# DRV8301.net
KiCad netlist of a schematic drawn in Altium Designer
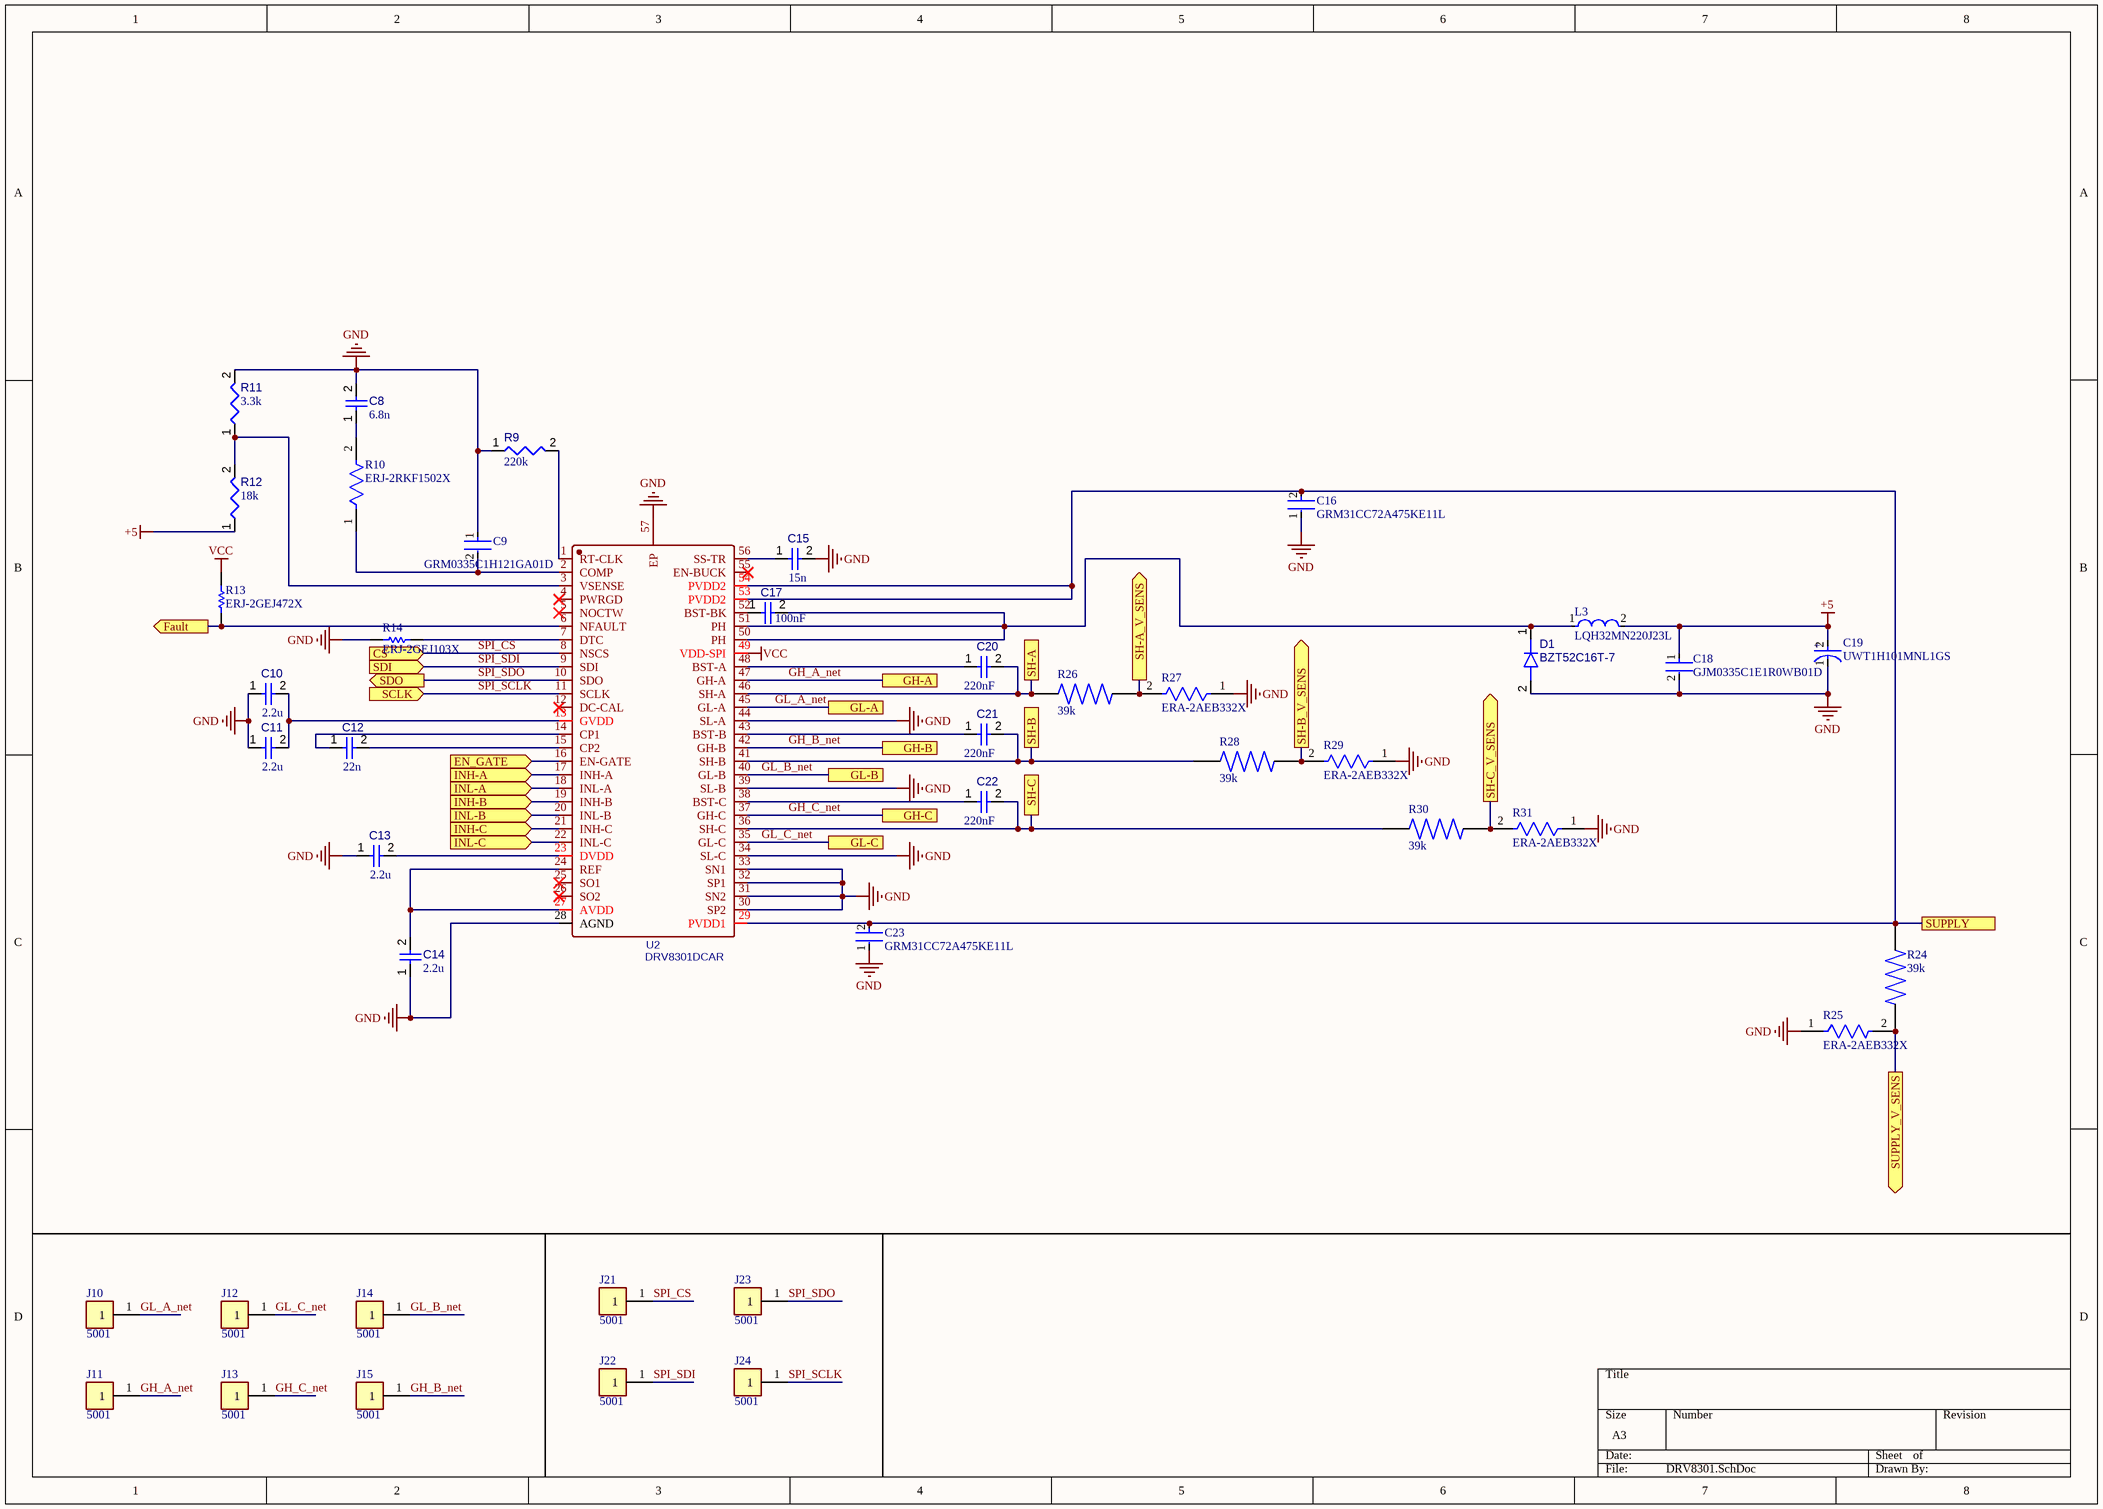
[diagram p0: DRV8301.SchDoc]

(export (version "E")
  (design (tool "Eeschema 10.0.6"))
  (components
    (comp (ref "C8")
      (value "6.8n")
      (footprint "CAP-0402")
      (fields (field (name "Comment") "C0402C682K5RECAUTO"))
      (libsource (lib "University of Michigan") (part "CAP-NP-2"))
    )
    (comp (ref "C9")
      (value "GRM0335C1H121GA01D")
      (footprint "FP-GRM033-0_03-IPC_A")
      (description "Chip Multilayer Ceramic Capacitors for General Purpose, 0201, 120pF, C0G, 30ppm/°C, 2%, 50V")
      (fields (field (name "TOLERANCE") "2%"))
      (libsource (lib "Altium Content Vault") (part "b4654b650e69147ec39a6b967a45e02"))
    )
    (comp (ref "C10")
      (value "2.2u")
      (footprint "CAP-0805")
      (description "ESD SMD Comm X7R 0805 (2012Metric) Ceramic Capacitor 0.079Lx0.049W 2.00mmx1.25mm X7R ±5% 2.2muF")
      (fields (field (name "Comment") "C0805C225J4REC7800"))
      (libsource (lib "University of Michigan") (part "CAP-NP-2"))
    )
    (comp (ref "C11")
      (value "2.2u")
      (footprint "CAP-0805")
      (description "ESD SMD Comm X7R 0805 (2012Metric) Ceramic Capacitor 0.079Lx0.049W 2.00mmx1.25mm X7R ±5% 2.2muF")
      (fields (field (name "Comment") "C0805C225J4REC7800"))
      (libsource (lib "University of Michigan") (part "CAP-NP-2"))
    )
    (comp (ref "C12")
      (value "22n")
      (footprint "CAP-0402")
      (fields (field (name "Comment") "C0402C223K5RECAUTO"))
      (libsource (lib "University of Michigan") (part "CAP-NP-2"))
    )
    (comp (ref "C13")
      (value "2.2u")
      (footprint "CAP-0805")
      (description "ESD SMD Comm X7R 0805 (2012Metric) Ceramic Capacitor 0.079Lx0.049W 2.00mmx1.25mm X7R ±5% 2.2muF")
      (fields (field (name "Comment") "C0805C225J4REC7800"))
      (libsource (lib "University of Michigan") (part "CAP-NP-2"))
    )
    (comp (ref "C14")
      (value "2.2u")
      (footprint "CAP-0805")
      (description "ESD SMD Comm X7R 0805 (2012Metric) Ceramic Capacitor 0.079Lx0.049W 2.00mmx1.25mm X7R ±5% 2.2muF")
      (fields (field (name "Comment") "C0805C225J4REC7800"))
      (libsource (lib "University of Michigan") (part "CAP-NP-2"))
    )
    (comp (ref "C15")
      (value "15n")
      (footprint "CAP-0402")
      (fields (field (name "Comment") "C0402C153J5REC7867"))
      (libsource (lib "University of Michigan") (part "CAP-NP-2"))
    )
    (comp (ref "C16")
      (value "GRM31CC72A475KE11L")
      (footprint "FP-GRM31C-0_3-e0_3_0_9-MFG")
      (description "Chip Multilayer Ceramic Capacitors for General Purpose, 1206, 4.7uF, X7S, 22%, 10%, 100V")
      (libsource (lib "Altium Content Vault") (part "f23184f103b6ebe33a8c269c53dcba6"))
    )
    (comp (ref "C17")
      (value "100nF")
      (footprint "CAP-0805")
      (description "Cap. SMD, 0805, X7R, 100nF, 20%, 50V,")
      (fields (field (name "Comment") "MT05B104M500BD"))
      (libsource (lib "University of Michigan") (part "CAP-NP-2"))
    )
    (comp (ref "C18")
      (value "GJM0335C1E1R0WB01D")
      (footprint "FP-GJM033-0_03-IPC_A")
      (description "Ceramic Capacitor 1pF ±0.05pF 25V C0G 0201 (0603 Metric)")
      (libsource (lib "Altium Content Vault") (part "b4654b650e69147ec39a6b967a45e02"))
    )
    (comp (ref "C19")
      (value "UWT1H101MNL1GS")
      (footprint "FP-UWT1H101MNL1GS-MFG")
      (description "CAP ALUM 100UF 20% 50V SMD")
      (fields (field (name "TOLERANCE") "20%") (field (name "VOLTAGE") "50V"))
      (libsource (lib "Altium Content Vault") (part "203bc49f2ac43e59fd269a8c329ed05"))
    )
    (comp (ref "C20")
      (value "220nF")
      (footprint "CAP-0805")
      (description "Cap Ceramic 0.22uF 100V X7R 5% SMD 0805 125°C T/R")
      (fields (field (name "Comment") "C0805C224J1REC7800"))
      (libsource (lib "University of Michigan") (part "CAP-NP-2"))
    )
    (comp (ref "C21")
      (value "220nF")
      (footprint "CAP-0805")
      (description "Cap Ceramic 0.22uF 100V X7R 5% SMD 0805 125°C T/R")
      (fields (field (name "Comment") "C0805C224J1REC7800"))
      (libsource (lib "University of Michigan") (part "CAP-NP-2"))
    )
    (comp (ref "C22")
      (value "220nF")
      (footprint "CAP-0805")
      (description "Cap Ceramic 0.22uF 100V X7R 5% SMD 0805 125°C T/R")
      (fields (field (name "Comment") "C0805C224J1REC7800"))
      (libsource (lib "University of Michigan") (part "CAP-NP-2"))
    )
    (comp (ref "C23")
      (value "GRM31CC72A475KE11L")
      (footprint "FP-GRM31C-0_3-e0_3_0_9-MFG")
      (description "Chip Multilayer Ceramic Capacitors for General Purpose, 1206, 4.7uF, X7S, 22%, 10%, 100V")
      (libsource (lib "Altium Content Vault") (part "f23184f103b6ebe33a8c269c53dcba6"))
    )
    (comp (ref "D1")
      (value "BZT52C16T-7")
      (footprint "SODFL160X65-2N")
      (description "Zener Diode, 16V V(Z), 5.56%, 0.3W, Silicon, Unidirectional")
      (libsource (lib "University of Michigan") (part "DIODE-2"))
    )
    (comp (ref "J10")
      (value "5001")
      (footprint "FP-5001-MFG")
      (description "PC TEST POINT MINIATURE BLACK")
      (libsource (lib "Altium Content Vault") (part "1e4615820a309e3ce90f9e6d957b7fa"))
    )
    (comp (ref "J11")
      (value "5001")
      (footprint "FP-5001-MFG")
      (description "PC TEST POINT MINIATURE BLACK")
      (libsource (lib "Altium Content Vault") (part "1e4615820a309e3ce90f9e6d957b7fa"))
    )
    (comp (ref "J12")
      (value "5001")
      (footprint "FP-5001-MFG")
      (description "PC TEST POINT MINIATURE BLACK")
      (libsource (lib "Altium Content Vault") (part "1e4615820a309e3ce90f9e6d957b7fa"))
    )
    (comp (ref "J13")
      (value "5001")
      (footprint "FP-5001-MFG")
      (description "PC TEST POINT MINIATURE BLACK")
      (libsource (lib "Altium Content Vault") (part "1e4615820a309e3ce90f9e6d957b7fa"))
    )
    (comp (ref "J14")
      (value "5001")
      (footprint "FP-5001-MFG")
      (description "PC TEST POINT MINIATURE BLACK")
      (libsource (lib "Altium Content Vault") (part "1e4615820a309e3ce90f9e6d957b7fa"))
    )
    (comp (ref "J15")
      (value "5001")
      (footprint "FP-5001-MFG")
      (description "PC TEST POINT MINIATURE BLACK")
      (libsource (lib "Altium Content Vault") (part "1e4615820a309e3ce90f9e6d957b7fa"))
    )
    (comp (ref "J21")
      (value "5001")
      (footprint "FP-5001-MFG")
      (description "PC TEST POINT MINIATURE BLACK")
      (libsource (lib "Altium Content Vault") (part "1e4615820a309e3ce90f9e6d957b7fa"))
    )
    (comp (ref "J22")
      (value "5001")
      (footprint "FP-5001-MFG")
      (description "PC TEST POINT MINIATURE BLACK")
      (libsource (lib "Altium Content Vault") (part "1e4615820a309e3ce90f9e6d957b7fa"))
    )
    (comp (ref "J23")
      (value "5001")
      (footprint "FP-5001-MFG")
      (description "PC TEST POINT MINIATURE BLACK")
      (libsource (lib "Altium Content Vault") (part "1e4615820a309e3ce90f9e6d957b7fa"))
    )
    (comp (ref "J24")
      (value "5001")
      (footprint "FP-5001-MFG")
      (description "PC TEST POINT MINIATURE BLACK")
      (libsource (lib "Altium Content Vault") (part "1e4615820a309e3ce90f9e6d957b7fa"))
    )
    (comp (ref "L3")
      (value "LQH32MN220J23L")
      (footprint "FP-LQH32CH_23-MFG")
      (description "Wire Wound Ferrite Inductor for General Circuits 22μH ±5% 2.8Ω 150mA 1210")
      (fields (field (name "TOLERANCE") "5%"))
      (libsource (lib "Altium Content Vault") (part "725321dda6339637d4d059423bc1c3c"))
    )
    (comp (ref "R9")
      (value "220k")
      (footprint "CAP-0603")
      (fields
        (field (name "POWER") "100mW")
        (field (name "TOLERANCE") "1%")
        (field (name "Comment") "WR06X2203FTL")
      )
      (libsource (lib "University of Michigan") (part "RES-2"))
    )
    (comp (ref "R10")
      (value "ERJ-2RKF1502X")
      (footprint "FP-ERJ2R-MFG")
      (description "RES SMD 15K OHM 1% 1/10W 0402")
      (fields
        (field (name "TOLERANCE") "1%")
        (field (name "OCTOPART") "https://octopart.com/erj-2rkf1502x-panasonic-55404985")
      )
      (libsource (lib "Altium Content Vault") (part "1029c3af85768c4190bb7ad29bc67b5"))
    )
    (comp (ref "R11")
      (value "3.3k")
      (footprint "CAP-0603")
      (fields
        (field (name "TOLERANCE") "1%")
        (field (name "POWER") "100mW")
        (field (name "Comment") "RMCF0603FT3K30")
      )
      (libsource (lib "University of Michigan") (part "RES-2"))
    )
    (comp (ref "R12")
      (value "18k")
      (footprint "CAP-0603")
      (fields
        (field (name "POWER") "100mW")
        (field (name "TOLERANCE") "1%")
        (field (name "Comment") "RMCF0603FT18K0")
      )
      (libsource (lib "University of Michigan") (part "RES-2"))
    )
    (comp (ref "R13")
      (value "ERJ-2GEJ472X")
      (footprint "RESC1005X40X25LL05T05")
      (fields (field (name "MANUFACTURER") "Panasonic"))
      (libsource (lib "Altium Content Vault") (part "RES"))
    )
    (comp (ref "R14")
      (value "ERJ-2GEJ103X")
      (footprint "RESC1005X40X25ML05T05")
      (fields (field (name "MANUFACTURER") "Panasonic"))
      (libsource (lib "Altium Content Vault") (part "RES"))
    )
    (comp (ref "R24")
      (value "39k")
      (footprint "RESC6332X120N")
      (description "3522 39K 5% 3W")
      (fields (field (name "MP") "352239KJT"))
      (libsource (lib "University of Michigan") (part "352239KJT"))
    )
    (comp (ref "R25")
      (value "ERA-2AEB332X")
      (footprint "FP-ERA2A-MFG")
      (fields (field (name "TOLERANCE") "0.1%"))
      (libsource (lib "Altium Content Vault") (part "1029c3af85768c4190bb7ad29bc67b5"))
    )
    (comp (ref "R26")
      (value "39k")
      (footprint "RESC6332X120N")
      (description "3522 39K 5% 3W")
      (fields (field (name "MP") "352239KJT"))
      (libsource (lib "University of Michigan") (part "352239KJT"))
    )
    (comp (ref "R27")
      (value "ERA-2AEB332X")
      (footprint "FP-ERA2A-MFG")
      (fields (field (name "TOLERANCE") "0.1%"))
      (libsource (lib "Altium Content Vault") (part "1029c3af85768c4190bb7ad29bc67b5"))
    )
    (comp (ref "R28")
      (value "39k")
      (footprint "RESC6332X120N")
      (description "3522 39K 5% 3W")
      (fields (field (name "MP") "352239KJT"))
      (libsource (lib "University of Michigan") (part "352239KJT"))
    )
    (comp (ref "R29")
      (value "ERA-2AEB332X")
      (footprint "FP-ERA2A-MFG")
      (fields (field (name "TOLERANCE") "0.1%"))
      (libsource (lib "Altium Content Vault") (part "1029c3af85768c4190bb7ad29bc67b5"))
    )
    (comp (ref "R30")
      (value "39k")
      (footprint "RESC6332X120N")
      (description "3522 39K 5% 3W")
      (fields (field (name "MP") "352239KJT"))
      (libsource (lib "University of Michigan") (part "352239KJT"))
    )
    (comp (ref "R31")
      (value "ERA-2AEB332X")
      (footprint "FP-ERA2A-MFG")
      (fields (field (name "TOLERANCE") "0.1%"))
      (libsource (lib "Altium Content Vault") (part "1029c3af85768c4190bb7ad29bc67b5"))
    )
    (comp (ref "U2")
      (value "DRV8301DCAR")
      (footprint "MasterLib:IC-HTSSOP-56-THERM")
      (fields (field (name "BOM_SUPPLIER PART") "C98969") (field (name "CONTRIBUTOR") "LCSC"))
      (libsource (lib "altium-import") (part "root_0_DRV8301DCAR_"))
    )
  )
  (nets
    (net (code "1") (name "+5") (class "Default")
      (node (ref "C18") (pin "1") (pinfunction "1_1") (pintype "passive"))
      (node (ref "C19") (pin "2") (pinfunction "A_2") (pintype "passive"))
      (node (ref "L3") (pin "2") (pinfunction "2_2") (pintype "passive"))
      (node (ref "R12") (pin "1") (pinfunction "1_1") (pintype "passive"))
    )
    (net (code "2") (name "/EN_GATE") (class "Default")
      (node (ref "U2") (pin "16") (pinfunction "EN-GATE_16") (pintype "passive"))
    )
    (net (code "3") (name "/Fault") (class "Default")
      (node (ref "R13") (pin "1") (pinfunction "1_1") (pintype "passive"))
      (node (ref "U2") (pin "6") (pinfunction "NFAULT_6") (pintype "passive"))
    )
    (net (code "4") (name "/GH_A_net") (class "Default")
      (node (ref "J11") (pin "1") (pinfunction "1_1") (pintype "passive"))
      (node (ref "U2") (pin "47") (pinfunction "GH-A_47") (pintype "passive"))
    )
    (net (code "5") (name "/GH_B_net") (class "Default")
      (node (ref "J15") (pin "1") (pinfunction "1_1") (pintype "passive"))
      (node (ref "U2") (pin "42") (pinfunction "GH-B_42") (pintype "passive"))
    )
    (net (code "6") (name "/GH_C_net") (class "Default")
      (node (ref "J13") (pin "1") (pinfunction "1_1") (pintype "passive"))
      (node (ref "U2") (pin "37") (pinfunction "GH-C_37") (pintype "passive"))
    )
    (net (code "7") (name "/GL_A_net") (class "Default")
      (node (ref "J10") (pin "1") (pinfunction "1_1") (pintype "passive"))
      (node (ref "U2") (pin "45") (pinfunction "GL-A_45") (pintype "passive"))
    )
    (net (code "8") (name "/GL_B_net") (class "Default")
      (node (ref "J14") (pin "1") (pinfunction "1_1") (pintype "passive"))
      (node (ref "U2") (pin "40") (pinfunction "GL-B_40") (pintype "passive"))
    )
    (net (code "9") (name "/GL_C_net") (class "Default")
      (node (ref "J12") (pin "1") (pinfunction "1_1") (pintype "passive"))
      (node (ref "U2") (pin "35") (pinfunction "GL-C_35") (pintype "passive"))
    )
    (net (code "10") (name "/INH-A") (class "Default")
      (node (ref "U2") (pin "17") (pinfunction "INH-A_17") (pintype "passive"))
    )
    (net (code "11") (name "/INH-B") (class "Default")
      (node (ref "U2") (pin "19") (pinfunction "INH-B_19") (pintype "passive"))
    )
    (net (code "12") (name "/INH-C") (class "Default")
      (node (ref "U2") (pin "21") (pinfunction "INH-C_21") (pintype "passive"))
    )
    (net (code "13") (name "/INL-A") (class "Default")
      (node (ref "U2") (pin "18") (pinfunction "INL-A_18") (pintype "passive"))
    )
    (net (code "14") (name "/INL-B") (class "Default")
      (node (ref "U2") (pin "20") (pinfunction "INL-B_20") (pintype "passive"))
    )
    (net (code "15") (name "/INL-C") (class "Default")
      (node (ref "U2") (pin "22") (pinfunction "INL-C_22") (pintype "passive"))
    )
    (net (code "16") (name "/SH-A") (class "Default")
      (node (ref "C20") (pin "2") (pinfunction "2_2") (pintype "passive"))
      (node (ref "R26") (pin "1") (pinfunction "1_1") (pintype "passive"))
      (node (ref "U2") (pin "46") (pinfunction "SH-A_46") (pintype "passive"))
    )
    (net (code "17") (name "/SH-A_V_SENS") (class "Default")
      (node (ref "R26") (pin "2") (pinfunction "2_2") (pintype "passive"))
      (node (ref "R27") (pin "2") (pinfunction "2_2") (pintype "passive"))
    )
    (net (code "18") (name "/SH-B") (class "Default")
      (node (ref "C21") (pin "2") (pinfunction "2_2") (pintype "passive"))
      (node (ref "R28") (pin "1") (pinfunction "1_1") (pintype "passive"))
      (node (ref "U2") (pin "41") (pinfunction "SH-B_41") (pintype "passive"))
    )
    (net (code "19") (name "/SH-B_V_SENS") (class "Default")
      (node (ref "R28") (pin "2") (pinfunction "2_2") (pintype "passive"))
      (node (ref "R29") (pin "2") (pinfunction "2_2") (pintype "passive"))
    )
    (net (code "20") (name "/SH-C") (class "Default")
      (node (ref "C22") (pin "2") (pinfunction "2_2") (pintype "passive"))
      (node (ref "R30") (pin "1") (pinfunction "1_1") (pintype "passive"))
      (node (ref "U2") (pin "36") (pinfunction "SH-C_36") (pintype "passive"))
    )
    (net (code "21") (name "/SH-C_V_SENS") (class "Default")
      (node (ref "R30") (pin "2") (pinfunction "2_2") (pintype "passive"))
      (node (ref "R31") (pin "2") (pinfunction "2_2") (pintype "passive"))
    )
    (net (code "22") (name "/SPI_CS") (class "Default")
      (node (ref "J21") (pin "1") (pinfunction "1_1") (pintype "passive"))
      (node (ref "U2") (pin "8") (pinfunction "NSCS_8") (pintype "passive"))
    )
    (net (code "23") (name "/SPI_SCLK") (class "Default")
      (node (ref "J24") (pin "1") (pinfunction "1_1") (pintype "passive"))
      (node (ref "U2") (pin "11") (pinfunction "SCLK_11") (pintype "passive"))
    )
    (net (code "24") (name "/SPI_SDI") (class "Default")
      (node (ref "J22") (pin "1") (pinfunction "1_1") (pintype "passive"))
      (node (ref "U2") (pin "9") (pinfunction "SDI_9") (pintype "passive"))
    )
    (net (code "25") (name "/SPI_SDO") (class "Default")
      (node (ref "J23") (pin "1") (pinfunction "1_1") (pintype "passive"))
      (node (ref "U2") (pin "10") (pinfunction "SDO_10") (pintype "passive"))
    )
    (net (code "26") (name "/SUPPLY") (class "Default")
      (node (ref "C16") (pin "2") (pinfunction "2_2") (pintype "passive"))
      (node (ref "C23") (pin "2") (pinfunction "2_2") (pintype "passive"))
      (node (ref "R24") (pin "1") (pinfunction "1_1") (pintype "passive"))
      (node (ref "U2") (pin "29") (pinfunction "PVDD1_29") (pintype "passive"))
      (node (ref "U2") (pin "53") (pinfunction "PVDD2_53") (pintype "passive"))
      (node (ref "U2") (pin "54") (pinfunction "PVDD2_54") (pintype "passive"))
    )
    (net (code "27") (name "/SUPPLY_V_SENS") (class "Default")
      (node (ref "R24") (pin "2") (pinfunction "2_2") (pintype "passive"))
      (node (ref "R25") (pin "2") (pinfunction "2_2") (pintype "passive"))
    )
    (net (code "28") (name "GND") (class "Default")
      (node (ref "C10") (pin "1") (pinfunction "1_1") (pintype "passive"))
      (node (ref "C11") (pin "1") (pinfunction "1_1") (pintype "passive"))
      (node (ref "C13") (pin "1") (pinfunction "1_1") (pintype "passive"))
      (node (ref "C14") (pin "1") (pinfunction "1_1") (pintype "passive"))
      (node (ref "C15") (pin "2") (pinfunction "2_2") (pintype "passive"))
      (node (ref "C16") (pin "1") (pinfunction "1_1") (pintype "passive"))
      (node (ref "C18") (pin "2") (pinfunction "2_2") (pintype "passive"))
      (node (ref "C19") (pin "1") (pinfunction "C_1") (pintype "passive"))
      (node (ref "C23") (pin "1") (pinfunction "1_1") (pintype "passive"))
      (node (ref "C8") (pin "2") (pinfunction "2_2") (pintype "passive"))
      (node (ref "C9") (pin "1") (pinfunction "1_1") (pintype "passive"))
      (node (ref "D1") (pin "2") (pinfunction "A_2") (pintype "passive"))
      (node (ref "R11") (pin "2") (pinfunction "2_2") (pintype "passive"))
      (node (ref "R14") (pin "1") (pinfunction "1_1") (pintype "passive"))
      (node (ref "R25") (pin "1") (pinfunction "1_1") (pintype "passive"))
      (node (ref "R27") (pin "1") (pinfunction "1_1") (pintype "passive"))
      (node (ref "R29") (pin "1") (pinfunction "1_1") (pintype "passive"))
      (node (ref "R31") (pin "1") (pinfunction "1_1") (pintype "passive"))
      (node (ref "R9") (pin "1") (pinfunction "1_1") (pintype "passive"))
      (node (ref "U2") (pin "28") (pinfunction "AGND_28") (pintype "power_in"))
      (node (ref "U2") (pin "30") (pinfunction "SP2_30") (pintype "passive"))
      (node (ref "U2") (pin "31") (pinfunction "SN2_31") (pintype "passive"))
      (node (ref "U2") (pin "32") (pinfunction "SP1_32") (pintype "passive"))
      (node (ref "U2") (pin "33") (pinfunction "SN1_33") (pintype "passive"))
      (node (ref "U2") (pin "34") (pinfunction "SL-C_34") (pintype "passive"))
      (node (ref "U2") (pin "39") (pinfunction "SL-B_39") (pintype "passive"))
      (node (ref "U2") (pin "44") (pinfunction "SL-A_44") (pintype "passive"))
      (node (ref "U2") (pin "57") (pinfunction "EP_57") (pintype "power_in"))
    )
    (net (code "29") (name "Net-(C8-Pad1)") (class "Default")
      (node (ref "C8") (pin "1") (pinfunction "1_1") (pintype "passive"))
      (node (ref "R10") (pin "2") (pinfunction "2_2") (pintype "passive"))
    )
    (net (code "30") (name "Net-(D1-K)") (class "Default")
      (node (ref "C17") (pin "2") (pinfunction "2_2") (pintype "passive"))
      (node (ref "D1") (pin "1") (pinfunction "K_1") (pintype "passive"))
      (node (ref "L3") (pin "1") (pinfunction "1_1") (pintype "passive"))
      (node (ref "U2") (pin "50") (pinfunction "PH_50") (pintype "passive"))
      (node (ref "U2") (pin "51") (pinfunction "PH_51") (pintype "passive"))
    )
    (net (code "31") (name "Net-(U2-AVDD)") (class "Default")
      (node (ref "C14") (pin "2") (pinfunction "2_2") (pintype "passive"))
      (node (ref "U2") (pin "24") (pinfunction "REF_24") (pintype "passive"))
      (node (ref "U2") (pin "27") (pinfunction "AVDD_27") (pintype "passive"))
    )
    (net (code "32") (name "Net-(U2-BST-A)") (class "Default")
      (node (ref "C20") (pin "1") (pinfunction "1_1") (pintype "passive"))
      (node (ref "U2") (pin "48") (pinfunction "BST-A_48") (pintype "passive"))
    )
    (net (code "33") (name "Net-(U2-BST-B)") (class "Default")
      (node (ref "C21") (pin "1") (pinfunction "1_1") (pintype "passive"))
      (node (ref "U2") (pin "43") (pinfunction "BST-B_43") (pintype "passive"))
    )
    (net (code "34") (name "Net-(U2-BST-BK)") (class "Default")
      (node (ref "C17") (pin "1") (pinfunction "1_1") (pintype "passive"))
      (node (ref "U2") (pin "52") (pinfunction "BST-BK_52") (pintype "passive"))
    )
    (net (code "35") (name "Net-(U2-BST-C)") (class "Default")
      (node (ref "C22") (pin "1") (pinfunction "1_1") (pintype "passive"))
      (node (ref "U2") (pin "38") (pinfunction "BST-C_38") (pintype "passive"))
    )
    (net (code "36") (name "Net-(U2-COMP)") (class "Default")
      (node (ref "C9") (pin "2") (pinfunction "2_2") (pintype "passive"))
      (node (ref "R10") (pin "1") (pinfunction "1_1") (pintype "passive"))
      (node (ref "U2") (pin "2") (pinfunction "COMP_2") (pintype "passive"))
    )
    (net (code "37") (name "Net-(U2-CP1)") (class "Default")
      (node (ref "C12") (pin "1") (pinfunction "1_1") (pintype "passive"))
      (node (ref "U2") (pin "14") (pinfunction "CP1_14") (pintype "passive"))
    )
    (net (code "38") (name "Net-(U2-CP2)") (class "Default")
      (node (ref "C12") (pin "2") (pinfunction "2_2") (pintype "passive"))
      (node (ref "U2") (pin "15") (pinfunction "CP2_15") (pintype "passive"))
    )
    (net (code "39") (name "Net-(U2-DTC)") (class "Default")
      (node (ref "R14") (pin "2") (pinfunction "2_2") (pintype "passive"))
      (node (ref "U2") (pin "7") (pinfunction "DTC_7") (pintype "passive"))
    )
    (net (code "40") (name "Net-(U2-DVDD)") (class "Default")
      (node (ref "C13") (pin "2") (pinfunction "2_2") (pintype "passive"))
      (node (ref "U2") (pin "23") (pinfunction "DVDD_23") (pintype "passive"))
    )
    (net (code "41") (name "Net-(U2-GVDD)") (class "Default")
      (node (ref "C10") (pin "2") (pinfunction "2_2") (pintype "passive"))
      (node (ref "C11") (pin "2") (pinfunction "2_2") (pintype "passive"))
      (node (ref "U2") (pin "13") (pinfunction "GVDD_13") (pintype "passive"))
    )
    (net (code "42") (name "Net-(U2-RT-CLK)") (class "Default")
      (node (ref "R9") (pin "2") (pinfunction "2_2") (pintype "passive"))
      (node (ref "U2") (pin "1") (pinfunction "RT-CLK_1") (pintype "passive"))
    )
    (net (code "43") (name "Net-(U2-SS-TR)") (class "Default")
      (node (ref "C15") (pin "1") (pinfunction "1_1") (pintype "passive"))
      (node (ref "U2") (pin "56") (pinfunction "SS-TR_56") (pintype "passive"))
    )
    (net (code "44") (name "Net-(U2-VSENSE)") (class "Default")
      (node (ref "R11") (pin "1") (pinfunction "1_1") (pintype "passive"))
      (node (ref "R12") (pin "2") (pinfunction "2_2") (pintype "passive"))
      (node (ref "U2") (pin "3") (pinfunction "VSENSE_3") (pintype "passive"))
    )
    (net (code "45") (name "VCC") (class "Default")
      (node (ref "R13") (pin "2") (pinfunction "2_2") (pintype "passive"))
      (node (ref "U2") (pin "49") (pinfunction "VDD-SPI_49") (pintype "passive"))
    )
    (net (code "46") (name "unconnected-(U2-DC-CAL-Pad12)") (class "Default")
      (node (ref "U2") (pin "12") (pinfunction "DC-CAL_12") (pintype "passive+no_connect"))
    )
    (net (code "47") (name "unconnected-(U2-EN-BUCK-Pad55)") (class "Default")
      (node (ref "U2") (pin "55") (pinfunction "EN-BUCK_55") (pintype "passive+no_connect"))
    )
    (net (code "48") (name "unconnected-(U2-NOCTW-Pad5)") (class "Default")
      (node (ref "U2") (pin "5") (pinfunction "NOCTW_5") (pintype "passive+no_connect"))
    )
    (net (code "49") (name "unconnected-(U2-PWRGD-Pad4)") (class "Default")
      (node (ref "U2") (pin "4") (pinfunction "PWRGD_4") (pintype "passive+no_connect"))
    )
    (net (code "50") (name "unconnected-(U2-SO1-Pad25)") (class "Default")
      (node (ref "U2") (pin "25") (pinfunction "SO1_25") (pintype "passive+no_connect"))
    )
    (net (code "51") (name "unconnected-(U2-SO2-Pad26)") (class "Default")
      (node (ref "U2") (pin "26") (pinfunction "SO2_26") (pintype "passive+no_connect"))
    )
  )
)
